# TPS61169_El.net
KiCad netlist of a schematic drawn in EAGLE
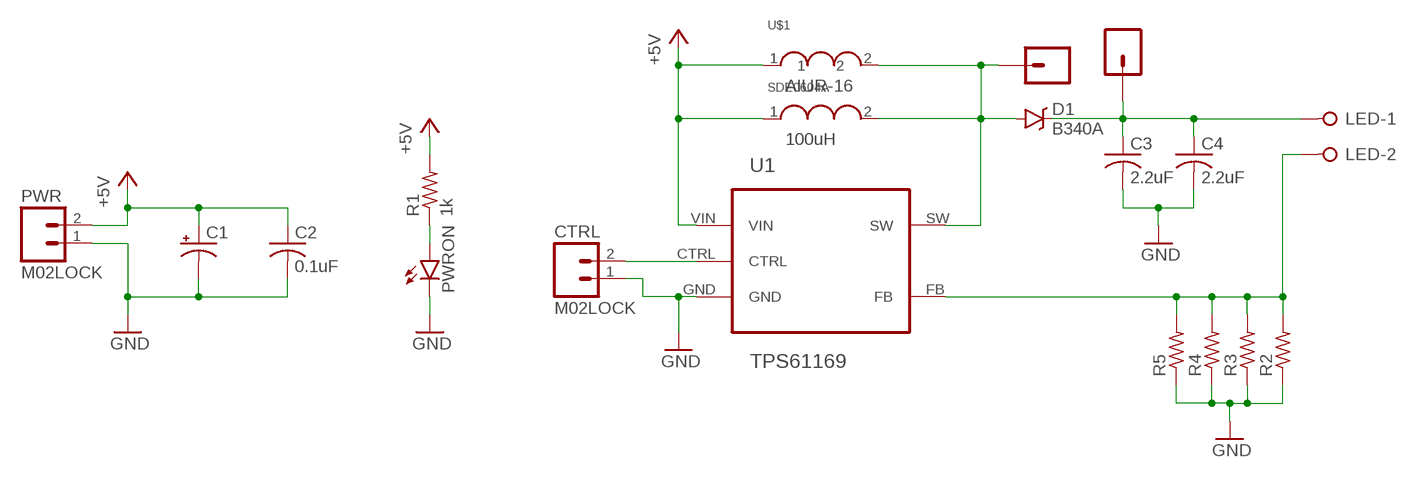
[diagram p0: schematic, sheet 1]

(export (version "E")
  (design (tool "Eeschema 10.0.6"))
  (components
    (comp (ref "AIUR-16")
      (value "100uH")
      (footprint "eagle-import:3MM_LEADS_7MM")
      (libsource (lib "eagle-import") (part "AIUR-16"))
    )
    (comp (ref "C1")
      (value "CPOL-USE2.5-7")
      (footprint "eagle-import:E2,5-7")
      (libsource (lib "eagle-import") (part "CPOL-USE2.5-7"))
    )
    (comp (ref "C2")
      (value "0.1uF")
      (footprint "eagle-import:C0805")
      (libsource (lib "eagle-import") (part "C-USC0805"))
    )
    (comp (ref "C3")
      (value "2.2uF")
      (footprint "eagle-import:C0805")
      (libsource (lib "eagle-import") (part "C-USC0805"))
    )
    (comp (ref "C4")
      (value "2.2uF")
      (footprint "eagle-import:C0805")
      (libsource (lib "eagle-import") (part "C-USC0805"))
    )
    (comp (ref "CTRL")
      (value "M02LOCK")
      (footprint "eagle-import:1X02_LOCK")
      (libsource (lib "eagle-import") (part "M02LOCK"))
    )
    (comp (ref "D1")
      (value "B340A")
      (footprint "eagle-import:SMA-DIODE")
      (libsource (lib "eagle-import") (part "DIODE-SCHOTTKY-B340A"))
    )
    (comp (ref "JP6")
      (value "M01SMDNS")
      (footprint "eagle-import:1X01NS")
      (libsource (lib "eagle-import") (part "M01SMDNS"))
    )
    (comp (ref "JP7")
      (value "M01SMDNS")
      (footprint "eagle-import:1X01NS")
      (libsource (lib "eagle-import") (part "M01SMDNS"))
    )
    (comp (ref "LED")
      (value "W237-02P")
      (footprint "eagle-import:W237-132")
      (libsource (lib "eagle-import") (part "W237-02P"))
    )
    (comp (ref "PWR")
      (value "M02LOCK")
      (footprint "eagle-import:1X02_LOCK")
      (libsource (lib "eagle-import") (part "M02LOCK"))
    )
    (comp (ref "PWRON")
      (value "LED1206")
      (footprint "eagle-import:LED-1206")
      (libsource (lib "eagle-import") (part "LED1206"))
    )
    (comp (ref "R1")
      (value "1k")
      (footprint "eagle-import:R0805")
      (libsource (lib "eagle-import") (part "R-US_R0805"))
    )
    (comp (ref "R2")
      (value "R-US_R0805")
      (footprint "eagle-import:R0805")
      (libsource (lib "eagle-import") (part "R-US_R0805"))
    )
    (comp (ref "R3")
      (value "R-US_R0805")
      (footprint "eagle-import:R0805")
      (libsource (lib "eagle-import") (part "R-US_R0805"))
    )
    (comp (ref "R4")
      (value "R-US_R0805")
      (footprint "eagle-import:R0805")
      (libsource (lib "eagle-import") (part "R-US_R0805"))
    )
    (comp (ref "R5")
      (value "R-US_R0805")
      (footprint "eagle-import:R0805")
      (libsource (lib "eagle-import") (part "R-US_R0805"))
    )
    (comp (ref "U$1")
      (value "SDE0604A")
      (footprint "eagle-import:BOURNS_SMD")
      (libsource (lib "eagle-import") (part "SDE0604A"))
    )
    (comp (ref "U1")
      (value "TPS61169")
      (footprint "eagle-import:SOT65P210X110-5N")
      (fields (field (name "MPN") "74AHCT1G04GW/T1"))
      (libsource (lib "eagle-import") (part "74AHCT1G04GW/T1"))
    )
  )
  (nets
    (net (code "1") (name "+5V") (class "Default")
      (node (ref "AIUR-16") (pin "1") (pinfunction "1_1") (pintype "bidirectional"))
      (node (ref "C1") (pin "+") (pinfunction "+_+") (pintype "passive"))
      (node (ref "C2") (pin "1") (pinfunction "1_1") (pintype "passive"))
      (node (ref "PWR") (pin "2") (pinfunction "2_2") (pintype "passive"))
      (node (ref "R1") (pin "2") (pinfunction "2_2") (pintype "passive"))
      (node (ref "U$1") (pin "1") (pinfunction "1_1") (pintype "bidirectional"))
      (node (ref "U1") (pin "VIN") (pinfunction "VIN_VIN") (pintype "power_in"))
    )
    (net (code "2") (name "GND") (class "Default")
      (node (ref "C1") (pin "-") (pinfunction "-_-") (pintype "passive"))
      (node (ref "C2") (pin "2") (pinfunction "2_2") (pintype "passive"))
      (node (ref "C3") (pin "2") (pinfunction "2_2") (pintype "passive"))
      (node (ref "C4") (pin "2") (pinfunction "2_2") (pintype "passive"))
      (node (ref "CTRL") (pin "1") (pinfunction "1_1") (pintype "passive"))
      (node (ref "PWR") (pin "1") (pinfunction "1_1") (pintype "passive"))
      (node (ref "PWRON") (pin "C") (pinfunction "C_C") (pintype "passive"))
      (node (ref "R2") (pin "1") (pinfunction "1_1") (pintype "passive"))
      (node (ref "R3") (pin "1") (pinfunction "1_1") (pintype "passive"))
      (node (ref "R4") (pin "1") (pinfunction "1_1") (pintype "passive"))
      (node (ref "R5") (pin "1") (pinfunction "1_1") (pintype "passive"))
      (node (ref "U1") (pin "GND") (pinfunction "GND_GND") (pintype "power_in"))
    )
    (net (code "3") (name "Net-(AIUR-16-Pad2)") (class "Default")
      (node (ref "AIUR-16") (pin "2") (pinfunction "2_2") (pintype "bidirectional"))
      (node (ref "D1") (pin "A") (pinfunction "A_A") (pintype "passive"))
      (node (ref "JP6") (pin "1") (pinfunction "1_1") (pintype "passive"))
      (node (ref "U$1") (pin "2") (pinfunction "2_2") (pintype "bidirectional"))
      (node (ref "U1") (pin "SW") (pinfunction "SW_SW") (pintype "output"))
    )
    (net (code "4") (name "Net-(CTRL-Pad2)") (class "Default")
      (node (ref "CTRL") (pin "2") (pinfunction "2_2") (pintype "passive"))
      (node (ref "U1") (pin "CTRL") (pinfunction "CTRL_CTRL") (pintype "input"))
    )
    (net (code "5") (name "Net-(LEDA-KL)") (class "Default")
      (node (ref "C3") (pin "1") (pinfunction "1_1") (pintype "passive"))
      (node (ref "C4") (pin "1") (pinfunction "1_1") (pintype "passive"))
      (node (ref "D1") (pin "C") (pinfunction "C_C") (pintype "passive"))
      (node (ref "JP7") (pin "1") (pinfunction "1_1") (pintype "passive"))
      (node (ref "LED") (pin "1") (pinfunction "KL_1") (pintype "passive"))
    )
    (net (code "6") (name "Net-(LEDB-KL)") (class "Default")
      (node (ref "LED") (pin "2") (pinfunction "KL_2") (pintype "passive"))
      (node (ref "R2") (pin "2") (pinfunction "2_2") (pintype "passive"))
      (node (ref "R3") (pin "2") (pinfunction "2_2") (pintype "passive"))
      (node (ref "R4") (pin "2") (pinfunction "2_2") (pintype "passive"))
      (node (ref "R5") (pin "2") (pinfunction "2_2") (pintype "passive"))
      (node (ref "U1") (pin "FB") (pinfunction "FB_FB") (pintype "input"))
    )
    (net (code "7") (name "Net-(PWRON-PadA)") (class "Default")
      (node (ref "PWRON") (pin "A") (pinfunction "A_A") (pintype "passive"))
      (node (ref "R1") (pin "1") (pinfunction "1_1") (pintype "passive"))
    )
  )
)
